# HBridge84.net
KiCad netlist of a schematic drawn in EAGLE
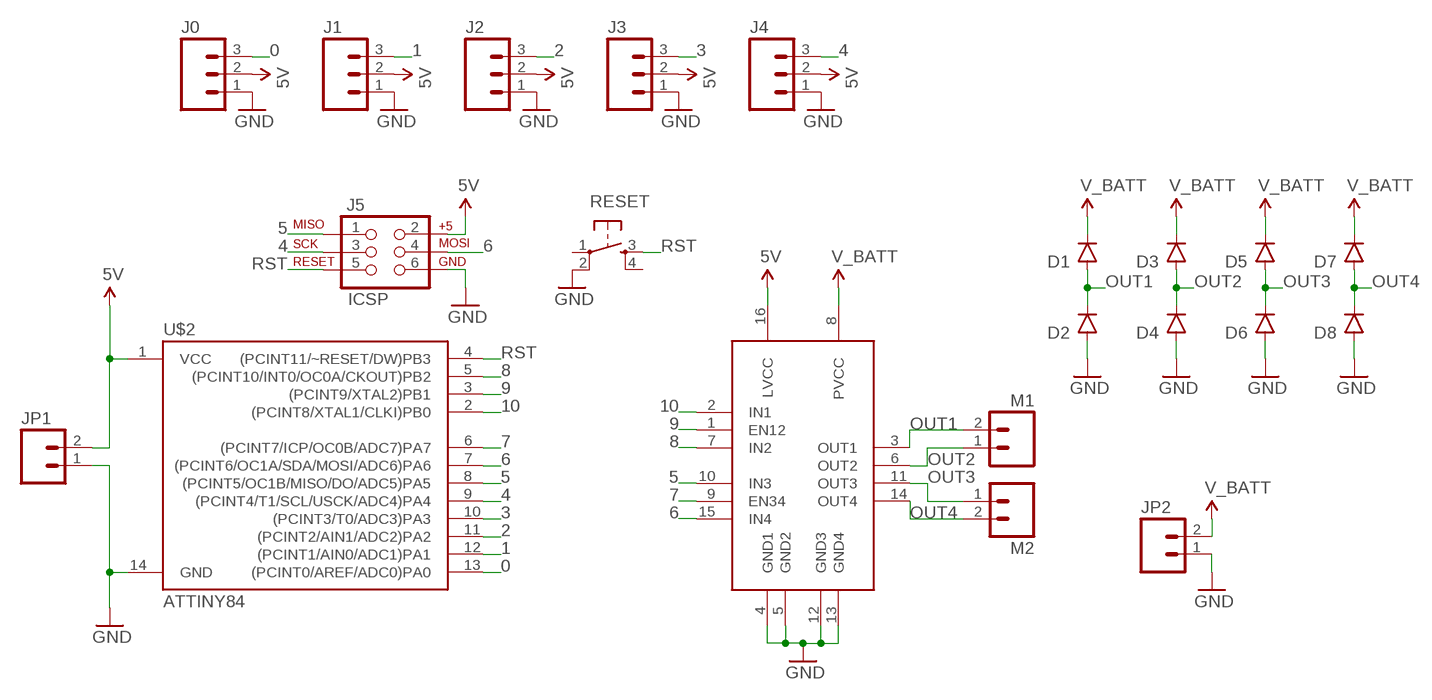
[diagram p0: schematic, sheet 1]

(export (version "E")
  (design (tool "Eeschema 10.0.6"))
  (components
    (comp (ref "D1")
      (value "DIODEPTH")
      (footprint "eagle-import:DIODE-1N4001")
      (libsource (lib "eagle-import") (part "DIODEPTH"))
    )
    (comp (ref "D2")
      (value "DIODEPTH")
      (footprint "eagle-import:DIODE-1N4001")
      (libsource (lib "eagle-import") (part "DIODEPTH"))
    )
    (comp (ref "D3")
      (value "DIODEPTH")
      (footprint "eagle-import:DIODE-1N4001")
      (libsource (lib "eagle-import") (part "DIODEPTH"))
    )
    (comp (ref "D4")
      (value "DIODEPTH")
      (footprint "eagle-import:DIODE-1N4001")
      (libsource (lib "eagle-import") (part "DIODEPTH"))
    )
    (comp (ref "D5")
      (value "DIODEPTH")
      (footprint "eagle-import:DIODE-1N4001")
      (libsource (lib "eagle-import") (part "DIODEPTH"))
    )
    (comp (ref "D6")
      (value "DIODEPTH")
      (footprint "eagle-import:DIODE-1N4001")
      (libsource (lib "eagle-import") (part "DIODEPTH"))
    )
    (comp (ref "D7")
      (value "DIODEPTH")
      (footprint "eagle-import:DIODE-1N4001")
      (libsource (lib "eagle-import") (part "DIODEPTH"))
    )
    (comp (ref "D8")
      (value "DIODEPTH")
      (footprint "eagle-import:DIODE-1N4001")
      (libsource (lib "eagle-import") (part "DIODEPTH"))
    )
    (comp (ref "J0")
      (value "M03PTH")
      (footprint "eagle-import:1X03")
      (libsource (lib "eagle-import") (part "M03PTH"))
    )
    (comp (ref "J1")
      (value "M03PTH")
      (footprint "eagle-import:1X03")
      (libsource (lib "eagle-import") (part "M03PTH"))
    )
    (comp (ref "J2")
      (value "M03PTH")
      (footprint "eagle-import:1X03")
      (libsource (lib "eagle-import") (part "M03PTH"))
    )
    (comp (ref "J3")
      (value "M03PTH")
      (footprint "eagle-import:1X03")
      (libsource (lib "eagle-import") (part "M03PTH"))
    )
    (comp (ref "J4")
      (value "M03PTH")
      (footprint "eagle-import:1X03")
      (libsource (lib "eagle-import") (part "M03PTH"))
    )
    (comp (ref "J5")
      (value "ICSP")
      (footprint "eagle-import:2X3-NS")
      (libsource (lib "eagle-import") (part "AVR_SPI_PRG_6LABELED"))
    )
    (comp (ref "JP1")
      (value "M02PTH")
      (footprint "eagle-import:1X02")
      (libsource (lib "eagle-import") (part "M02PTH"))
    )
    (comp (ref "JP2")
      (value "M02PTH")
      (footprint "eagle-import:1X02")
      (libsource (lib "eagle-import") (part "M02PTH"))
    )
    (comp (ref "M1")
      (value "M02PTH")
      (footprint "eagle-import:1X02")
      (libsource (lib "eagle-import") (part "M02PTH"))
    )
    (comp (ref "M2")
      (value "M02PTH")
      (footprint "eagle-import:1X02")
      (libsource (lib "eagle-import") (part "M02PTH"))
    )
    (comp (ref "RESET")
      (value "TAC_SWITCHPTH")
      (footprint "eagle-import:TACTILE-PTH")
      (libsource (lib "eagle-import") (part "TAC_SWITCHPTH"))
    )
    (comp (ref "SN754410")
      (value "SN754410")
      (footprint "eagle-import:DIP16")
      (libsource (lib "eagle-import") (part "SN754410"))
    )
    (comp (ref "U$2")
      (value "ATTINY84")
      (footprint "eagle-import:DIL14")
      (libsource (lib "eagle-import") (part "ATTINY84ATTINY84-20PU"))
    )
  )
  (nets
    (net (code "1") (name "/0") (class "Default")
      (node (ref "J0") (pin "3") (pinfunction "3_3") (pintype "passive"))
      (node (ref "U$2") (pin "13") (pinfunction "(PCINT0/AREF/ADC0)PA0_13") (pintype "bidirectional"))
    )
    (net (code "2") (name "/1") (class "Default")
      (node (ref "J1") (pin "3") (pinfunction "3_3") (pintype "passive"))
      (node (ref "U$2") (pin "12") (pinfunction "(PCINT1/AIN0/ADC1)PA1_12") (pintype "bidirectional"))
    )
    (net (code "3") (name "/2") (class "Default")
      (node (ref "J2") (pin "3") (pinfunction "3_3") (pintype "passive"))
      (node (ref "U$2") (pin "11") (pinfunction "(PCINT2/AIN1/ADC2)PA2_11") (pintype "bidirectional"))
    )
    (net (code "4") (name "/3") (class "Default")
      (node (ref "J3") (pin "3") (pinfunction "3_3") (pintype "passive"))
      (node (ref "U$2") (pin "10") (pinfunction "(PCINT3/T0/ADC3)PA3_10") (pintype "bidirectional"))
    )
    (net (code "5") (name "/4") (class "Default")
      (node (ref "J4") (pin "3") (pinfunction "3_3") (pintype "passive"))
      (node (ref "J5") (pin "3") (pinfunction "SCK_3") (pintype "passive"))
      (node (ref "U$2") (pin "9") (pinfunction "(PCINT4/T1/SCL/USCK/ADC4)PA4_9") (pintype "bidirectional"))
    )
    (net (code "6") (name "/5") (class "Default")
      (node (ref "J5") (pin "1") (pinfunction "MISO_1") (pintype "passive"))
      (node (ref "SN754410") (pin "10") (pinfunction "IN3_10") (pintype "bidirectional"))
      (node (ref "U$2") (pin "8") (pinfunction "(PCINT5/OC1B/MISO/DO/ADC5)PA5_8") (pintype "bidirectional"))
    )
    (net (code "7") (name "/6") (class "Default")
      (node (ref "J5") (pin "4") (pinfunction "MOSI_4") (pintype "passive"))
      (node (ref "SN754410") (pin "15") (pinfunction "IN4_15") (pintype "bidirectional"))
      (node (ref "U$2") (pin "7") (pinfunction "(PCINT6/OC1A/SDA/MOSI/ADC6)PA6_7") (pintype "bidirectional"))
    )
    (net (code "8") (name "/7") (class "Default")
      (node (ref "SN754410") (pin "9") (pinfunction "EN34_9") (pintype "bidirectional"))
      (node (ref "U$2") (pin "6") (pinfunction "(PCINT7/ICP/OC0B/ADC7)PA7_6") (pintype "bidirectional"))
    )
    (net (code "9") (name "/8") (class "Default")
      (node (ref "SN754410") (pin "7") (pinfunction "IN2_7") (pintype "bidirectional"))
      (node (ref "U$2") (pin "5") (pinfunction "(PCINT10/INT0/OC0A/CKOUT)PB2_5") (pintype "bidirectional"))
    )
    (net (code "10") (name "/9") (class "Default")
      (node (ref "SN754410") (pin "1") (pinfunction "EN12_1") (pintype "bidirectional"))
      (node (ref "U$2") (pin "3") (pinfunction "(PCINT9/XTAL2)PB1_3") (pintype "bidirectional"))
    )
    (net (code "11") (name "/10") (class "Default")
      (node (ref "SN754410") (pin "2") (pinfunction "IN1_2") (pintype "bidirectional"))
      (node (ref "U$2") (pin "2") (pinfunction "(PCINT8/XTAL1/CLKI)PB0_2") (pintype "bidirectional"))
    )
    (net (code "12") (name "/OUT1") (class "Default")
      (node (ref "D1") (pin "A") (pinfunction "A_A") (pintype "passive"))
      (node (ref "D2") (pin "C") (pinfunction "C_C") (pintype "passive"))
      (node (ref "M1") (pin "2") (pinfunction "2_2") (pintype "passive"))
      (node (ref "SN754410") (pin "3") (pinfunction "OUT1_3") (pintype "bidirectional"))
    )
    (net (code "13") (name "/OUT2") (class "Default")
      (node (ref "D3") (pin "A") (pinfunction "A_A") (pintype "passive"))
      (node (ref "D4") (pin "C") (pinfunction "C_C") (pintype "passive"))
      (node (ref "M1") (pin "1") (pinfunction "1_1") (pintype "passive"))
      (node (ref "SN754410") (pin "6") (pinfunction "OUT2_6") (pintype "bidirectional"))
    )
    (net (code "14") (name "/OUT3") (class "Default")
      (node (ref "D5") (pin "A") (pinfunction "A_A") (pintype "passive"))
      (node (ref "D6") (pin "C") (pinfunction "C_C") (pintype "passive"))
      (node (ref "M2") (pin "1") (pinfunction "1_1") (pintype "passive"))
      (node (ref "SN754410") (pin "11") (pinfunction "OUT3_11") (pintype "bidirectional"))
    )
    (net (code "15") (name "/OUT4") (class "Default")
      (node (ref "D7") (pin "A") (pinfunction "A_A") (pintype "passive"))
      (node (ref "D8") (pin "C") (pinfunction "C_C") (pintype "passive"))
      (node (ref "M2") (pin "2") (pinfunction "2_2") (pintype "passive"))
      (node (ref "SN754410") (pin "14") (pinfunction "OUT4_14") (pintype "bidirectional"))
    )
    (net (code "16") (name "/RST") (class "Default")
      (node (ref "J5") (pin "5") (pinfunction "RST_5") (pintype "passive"))
      (node (ref "RESET") (pin "3") (pinfunction "3_3") (pintype "passive"))
      (node (ref "U$2") (pin "4") (pinfunction "(PCINT11/~{RESET/DW})PB3_4") (pintype "bidirectional"))
    )
    (net (code "17") (name "5V") (class "Default")
      (node (ref "J0") (pin "2") (pinfunction "2_2") (pintype "passive"))
      (node (ref "J1") (pin "2") (pinfunction "2_2") (pintype "passive"))
      (node (ref "J2") (pin "2") (pinfunction "2_2") (pintype "passive"))
      (node (ref "J3") (pin "2") (pinfunction "2_2") (pintype "passive"))
      (node (ref "J4") (pin "2") (pinfunction "2_2") (pintype "passive"))
      (node (ref "J5") (pin "2") (pinfunction "V+_2") (pintype "passive"))
      (node (ref "JP1") (pin "2") (pinfunction "2_2") (pintype "passive"))
      (node (ref "SN754410") (pin "16") (pinfunction "LVCC_16") (pintype "bidirectional"))
      (node (ref "U$2") (pin "1") (pinfunction "VCC_1") (pintype "bidirectional"))
    )
    (net (code "18") (name "GND") (class "Default")
      (node (ref "D2") (pin "A") (pinfunction "A_A") (pintype "passive"))
      (node (ref "D4") (pin "A") (pinfunction "A_A") (pintype "passive"))
      (node (ref "D6") (pin "A") (pinfunction "A_A") (pintype "passive"))
      (node (ref "D8") (pin "A") (pinfunction "A_A") (pintype "passive"))
      (node (ref "J0") (pin "1") (pinfunction "1_1") (pintype "passive"))
      (node (ref "J1") (pin "1") (pinfunction "1_1") (pintype "passive"))
      (node (ref "J2") (pin "1") (pinfunction "1_1") (pintype "passive"))
      (node (ref "J3") (pin "1") (pinfunction "1_1") (pintype "passive"))
      (node (ref "J4") (pin "1") (pinfunction "1_1") (pintype "passive"))
      (node (ref "J5") (pin "6") (pinfunction "GND_6") (pintype "passive"))
      (node (ref "JP1") (pin "1") (pinfunction "1_1") (pintype "passive"))
      (node (ref "JP2") (pin "1") (pinfunction "1_1") (pintype "passive"))
      (node (ref "RESET") (pin "2") (pinfunction "2_2") (pintype "passive"))
      (node (ref "SN754410") (pin "12") (pinfunction "GND3_12") (pintype "bidirectional"))
      (node (ref "SN754410") (pin "13") (pinfunction "GND4_13") (pintype "bidirectional"))
      (node (ref "SN754410") (pin "4") (pinfunction "GND1_4") (pintype "bidirectional"))
      (node (ref "SN754410") (pin "5") (pinfunction "GND2_5") (pintype "bidirectional"))
      (node (ref "U$2") (pin "14") (pinfunction "GND_14") (pintype "bidirectional"))
    )
    (net (code "19") (name "V_BATT") (class "Default")
      (node (ref "D1") (pin "C") (pinfunction "C_C") (pintype "passive"))
      (node (ref "D3") (pin "C") (pinfunction "C_C") (pintype "passive"))
      (node (ref "D5") (pin "C") (pinfunction "C_C") (pintype "passive"))
      (node (ref "D7") (pin "C") (pinfunction "C_C") (pintype "passive"))
      (node (ref "JP2") (pin "2") (pinfunction "2_2") (pintype "passive"))
      (node (ref "SN754410") (pin "8") (pinfunction "PVCC_8") (pintype "bidirectional"))
    )
    (net (code "20") (name "unconnected-(RESET-Pad1)") (class "Default")
      (node (ref "RESET") (pin "1") (pinfunction "1_1") (pintype "passive"))
    )
    (net (code "21") (name "unconnected-(RESET-Pad4)") (class "Default")
      (node (ref "RESET") (pin "4") (pinfunction "4_4") (pintype "passive"))
    )
  )
)
